# attinier85-motherboard-pth-mk-2_0.net
KiCad netlist of a schematic drawn in EAGLE
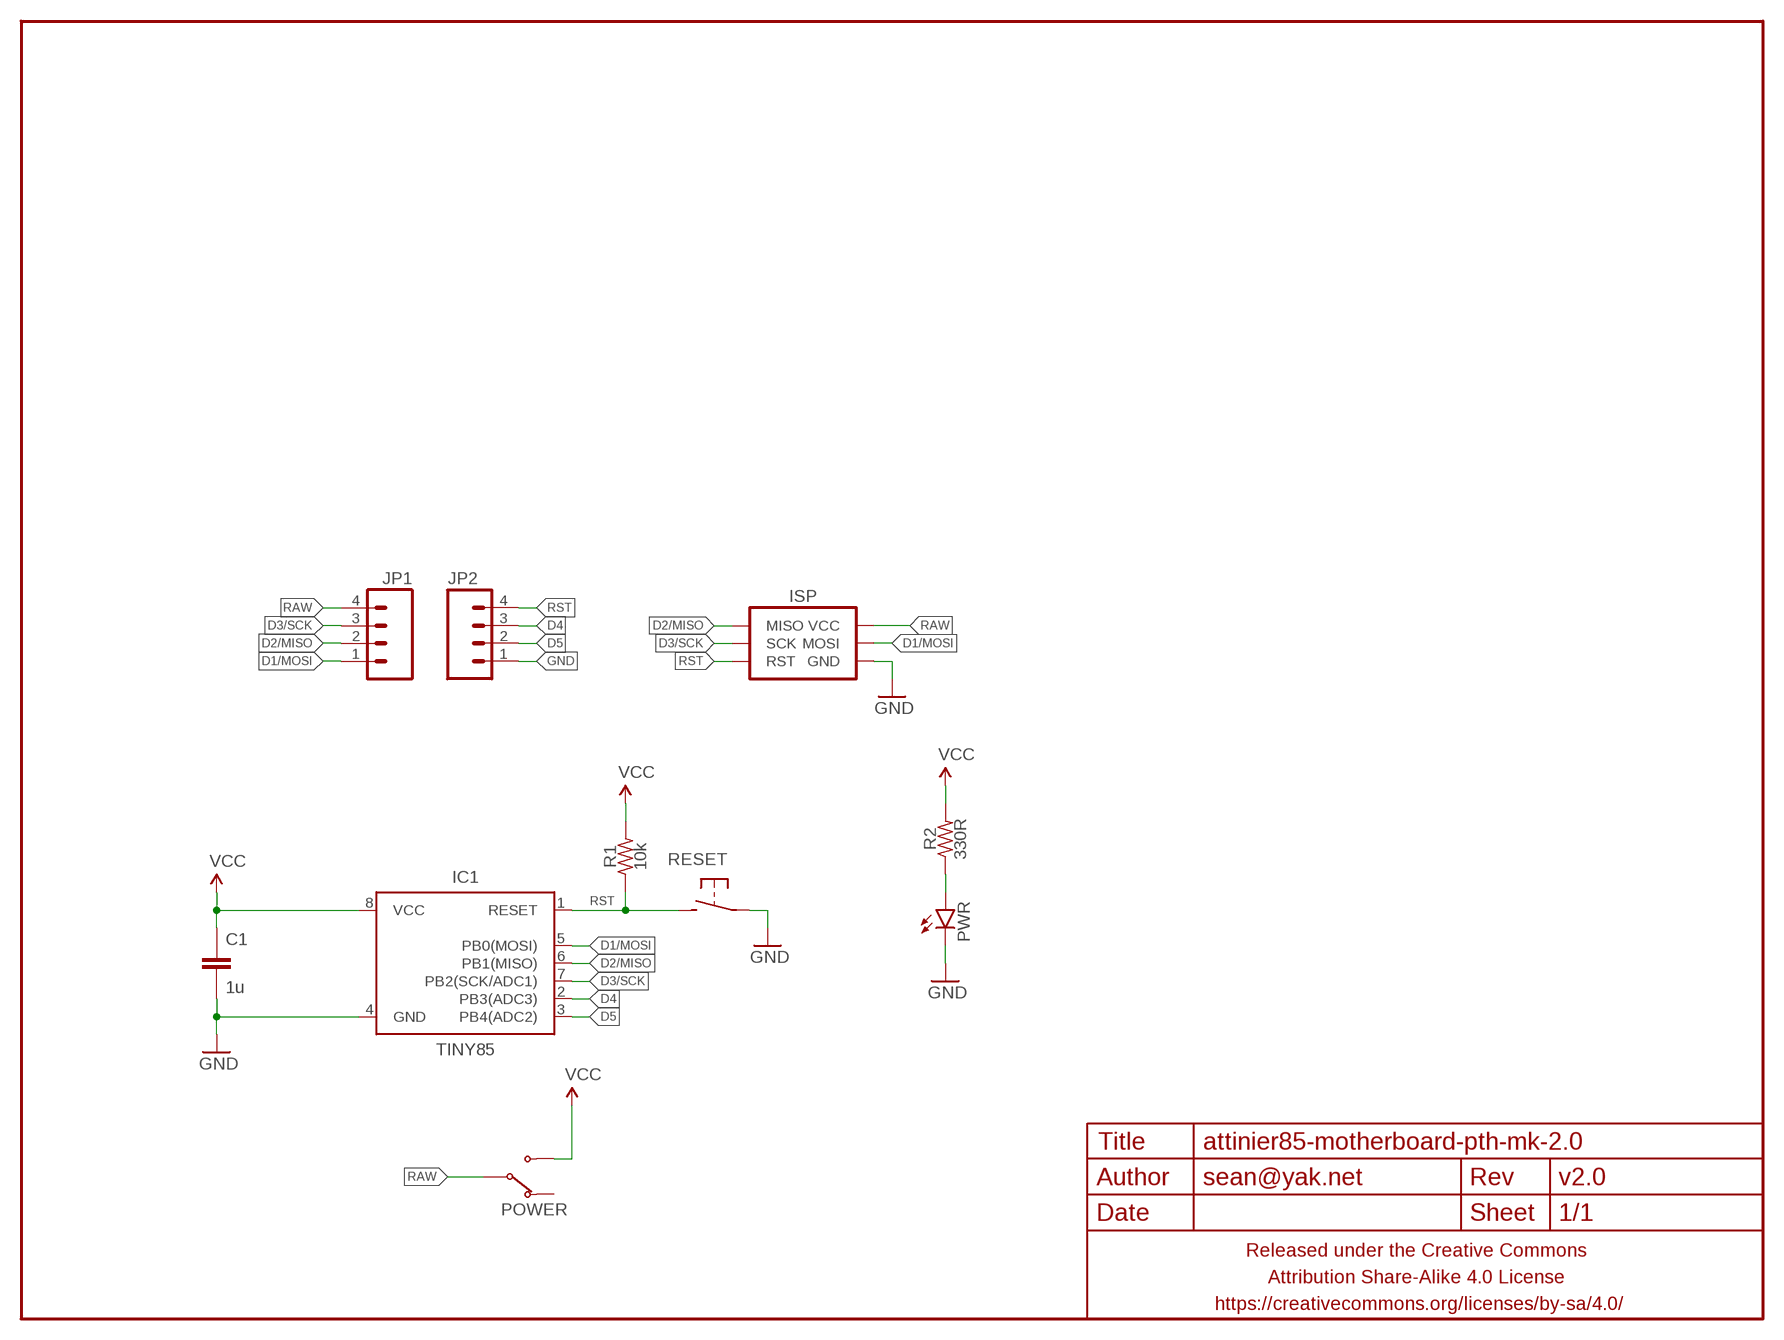
[diagram p0: schematic, sheet 1]

(export (version "E")
  (design (tool "Eeschema 10.0.6"))
  (components
    (comp (ref "C1")
      (value "1u")
      (footprint "eagle-import:C025-024X044")
      (libsource (lib "eagle-import") (part "CAPACITOR-CERAMIC025-024X044"))
    )
    (comp (ref "FRAME1")
      (value "FRAME-LETTERNO_PACKAGE")
      (footprint "eagle-import:DUMMY")
      (fields (field (name "DESIGNER") "sean@yak.net") (field (name "VERSION") "v2.0"))
      (libsource (lib "eagle-import") (part "FRAME-LETTERNO_PACKAGE"))
    )
    (comp (ref "IC1")
      (value "TINY85")
      (footprint "eagle-import:DIP08")
      (libsource (lib "eagle-import") (part "ATTINY45TINY85-20-DIP"))
    )
    (comp (ref "ISP")
      (value "AVR_SPI_PRG_6PTH")
      (footprint "eagle-import:2X3")
      (libsource (lib "eagle-import") (part "AVR_SPI_PRG_6PTH"))
    )
    (comp (ref "JP1")
      (value "M04PTH")
      (footprint "eagle-import:1X04-PTH-VERT")
      (libsource (lib "eagle-import") (part "M04PTH"))
    )
    (comp (ref "JP2")
      (value "M04PTH")
      (footprint "eagle-import:1X04-PTH-VERT")
      (libsource (lib "eagle-import") (part "M04PTH"))
    )
    (comp (ref "POWER")
      (value "SWITCH-SPDTPTH-RA-2.54MM-CENTERED")
      (footprint "eagle-import:SPDT-RA-2.54MM-CENTERED")
      (libsource (lib "eagle-import") (part "SWITCH-SPDTPTH-RA-2.54MM-CENTERED"))
    )
    (comp (ref "PWR")
      (value "LED3MM-LESS")
      (footprint "eagle-import:LED3MM-LESSSILK")
      (libsource (lib "eagle-import") (part "LED3MM-LESS"))
    )
    (comp (ref "R1")
      (value "10k")
      (footprint "eagle-import:RESISTOR-AXIAL-PTH-5.08MM")
      (libsource (lib "eagle-import") (part "RESISTORPTH-AXIAL-5.08MM"))
    )
    (comp (ref "R2")
      (value "330R")
      (footprint "eagle-import:RESISTOR-AXIAL-PTH-5.08MM")
      (libsource (lib "eagle-import") (part "RESISTORPTH-AXIAL-5.08MM"))
    )
    (comp (ref "RESET")
      (value "DTS-6MM")
      (footprint "eagle-import:DTS-3-SMALL-PADS")
      (libsource (lib "eagle-import") (part "SPST-NO-TACT3MM-PTH-SMALL-PADS"))
    )
  )
  (nets
    (net (code "1") (name "D1{slash}MOSI") (class "Default")
      (node (ref "IC1") (pin "5") (pinfunction "PB0(MOSI)_5") (pintype "bidirectional"))
      (node (ref "ISP") (pin "4") (pinfunction "MOSI_4") (pintype "passive"))
      (node (ref "JP1") (pin "1") (pinfunction "1_1") (pintype "passive"))
    )
    (net (code "2") (name "D2{slash}MISO") (class "Default")
      (node (ref "IC1") (pin "6") (pinfunction "PB1(MISO)_6") (pintype "bidirectional"))
      (node (ref "ISP") (pin "1") (pinfunction "MISO_1") (pintype "passive"))
      (node (ref "JP1") (pin "2") (pinfunction "2_2") (pintype "passive"))
    )
    (net (code "3") (name "D3{slash}SCK") (class "Default")
      (node (ref "IC1") (pin "7") (pinfunction "PB2(SCK/ADC1)_7") (pintype "bidirectional"))
      (node (ref "ISP") (pin "3") (pinfunction "SCK_3") (pintype "passive"))
      (node (ref "JP1") (pin "3") (pinfunction "3_3") (pintype "passive"))
    )
    (net (code "4") (name "D4") (class "Default")
      (node (ref "IC1") (pin "2") (pinfunction "PB3(ADC3)_2") (pintype "bidirectional"))
      (node (ref "JP2") (pin "3") (pinfunction "3_3") (pintype "passive"))
    )
    (net (code "5") (name "D5") (class "Default")
      (node (ref "IC1") (pin "3") (pinfunction "PB4(ADC2)_3") (pintype "bidirectional"))
      (node (ref "JP2") (pin "2") (pinfunction "2_2") (pintype "passive"))
    )
    (net (code "6") (name "GND") (class "Default")
      (node (ref "C1") (pin "2") (pinfunction "2_2") (pintype "passive"))
      (node (ref "IC1") (pin "4") (pinfunction "GND_4") (pintype "bidirectional"))
      (node (ref "ISP") (pin "6") (pinfunction "GND_6") (pintype "passive"))
      (node (ref "JP2") (pin "1") (pinfunction "1_1") (pintype "passive"))
      (node (ref "PWR") (pin "K") (pinfunction "C_K") (pintype "passive"))
      (node (ref "RESET") (pin "1") (pinfunction "1_1") (pintype "passive"))
    )
    (net (code "7") (name "Net-(R2-1)") (class "Default")
      (node (ref "PWR") (pin "A") (pinfunction "A_A") (pintype "passive"))
      (node (ref "R2") (pin "P$1") (pinfunction "1_P$1") (pintype "passive"))
    )
    (net (code "8") (name "RAW") (class "Default")
      (node (ref "ISP") (pin "2") (pinfunction "VCC_2") (pintype "passive"))
      (node (ref "JP1") (pin "4") (pinfunction "4_4") (pintype "passive"))
      (node (ref "POWER") (pin "2") (pinfunction "COM_2") (pintype "passive"))
    )
    (net (code "9") (name "RST") (class "Default")
      (node (ref "IC1") (pin "1") (pinfunction "RESET_1") (pintype "bidirectional"))
      (node (ref "ISP") (pin "5") (pinfunction "RST_5") (pintype "passive"))
      (node (ref "JP2") (pin "4") (pinfunction "4_4") (pintype "passive"))
      (node (ref "R1") (pin "P$1") (pinfunction "1_P$1") (pintype "passive"))
      (node (ref "RESET") (pin "2") (pinfunction "2_2") (pintype "passive"))
    )
    (net (code "10") (name "VCC") (class "Default")
      (node (ref "C1") (pin "1") (pinfunction "1_1") (pintype "passive"))
      (node (ref "IC1") (pin "8") (pinfunction "VCC_8") (pintype "bidirectional"))
      (node (ref "POWER") (pin "3") (pinfunction "NO_3") (pintype "passive"))
      (node (ref "R1") (pin "P$2") (pinfunction "2_P$2") (pintype "passive"))
      (node (ref "R2") (pin "P$2") (pinfunction "2_P$2") (pintype "passive"))
    )
    (net (code "11") (name "unconnected-(POWER-NC-Pad1)") (class "Default")
      (node (ref "POWER") (pin "1") (pinfunction "NC_1") (pintype "passive"))
    )
  )
)
